# ZX_Gesture_Sensor_SMD.net
KiCad netlist of a schematic drawn in EAGLE
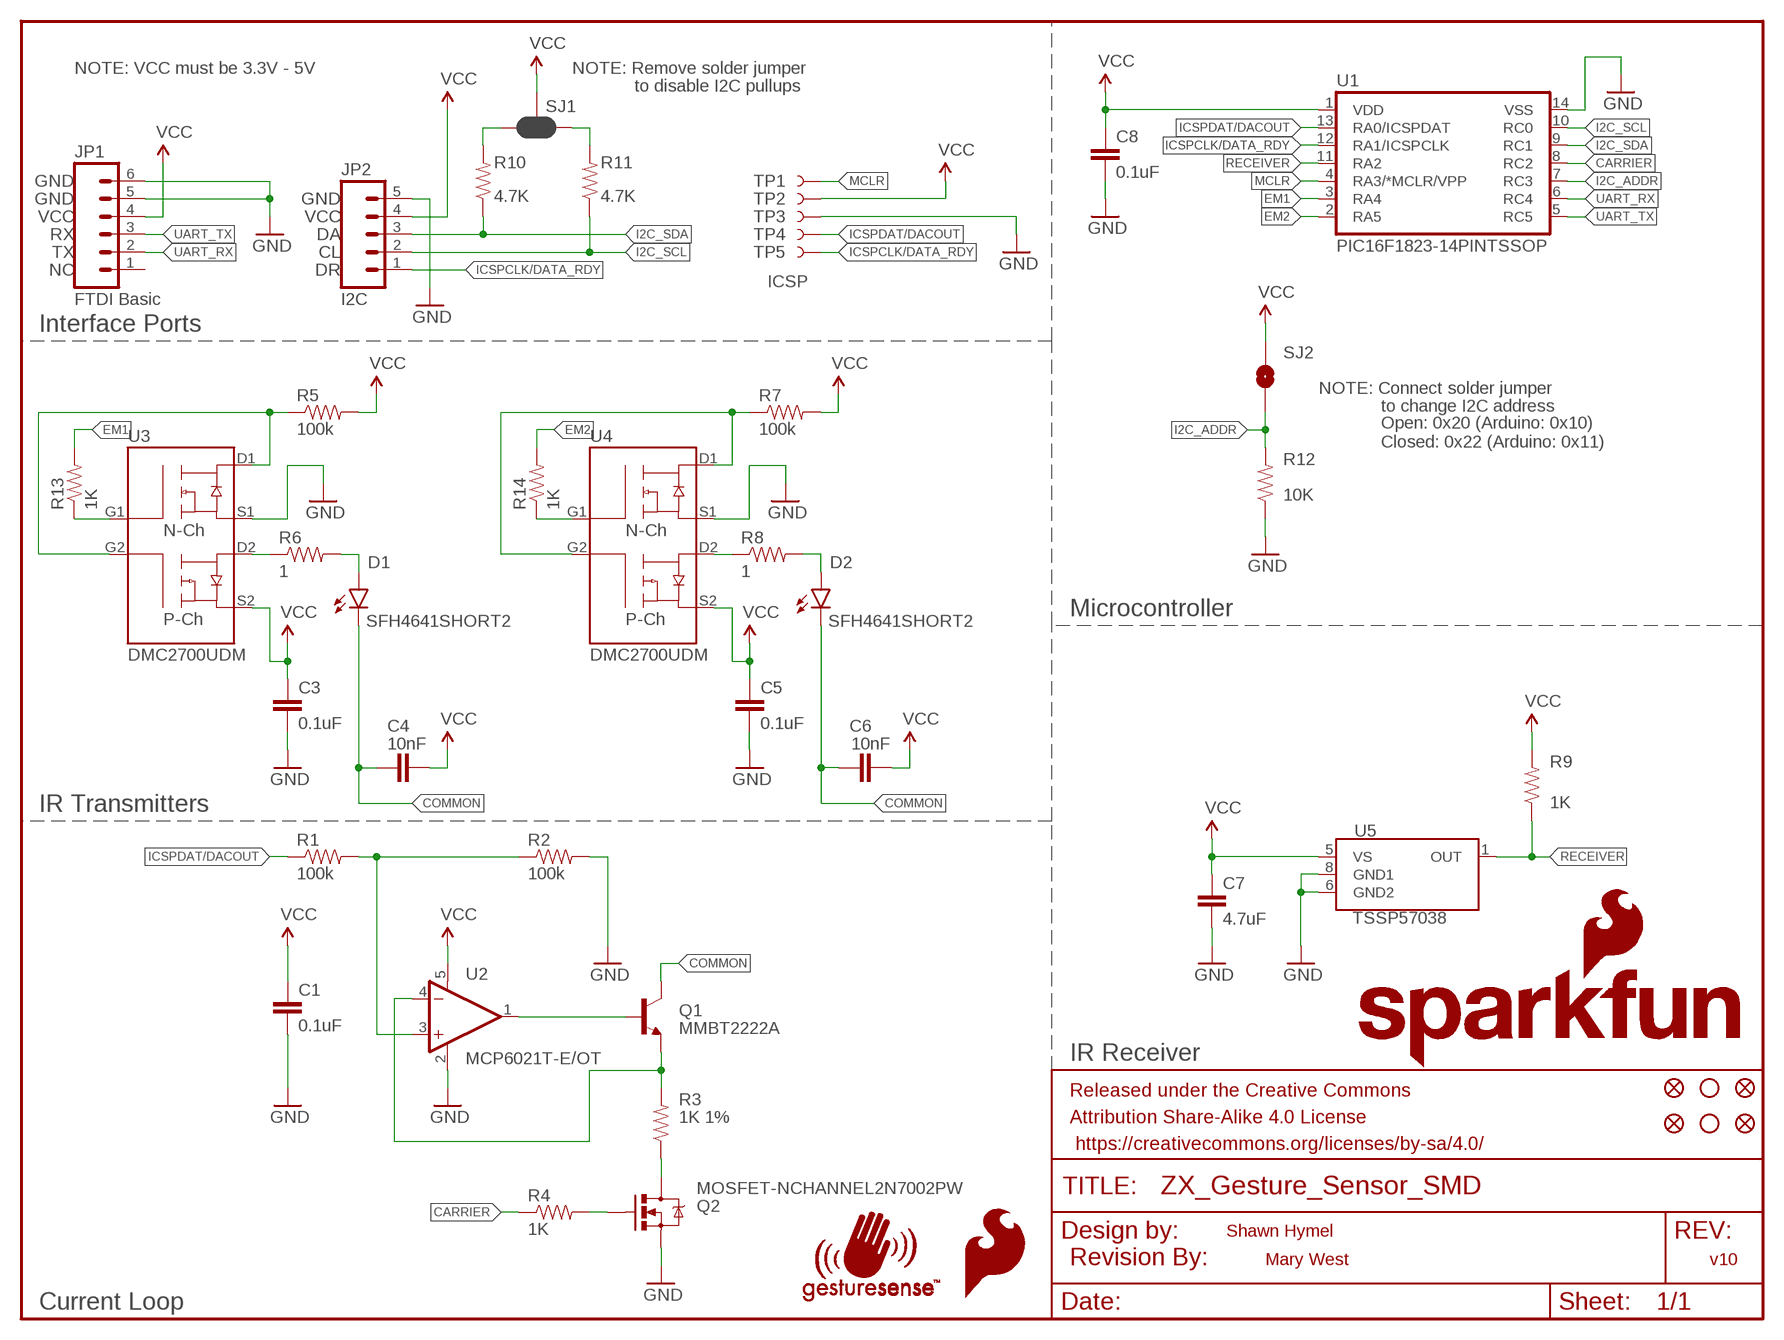
[diagram p0: schematic, sheet 1]

(export (version "E")
  (design (tool "Eeschema 10.0.6"))
  (components
    (comp (ref "C1")
      (value "0.1uF")
      (footprint "eagle-import:0603-CAP")
      (libsource (lib "eagle-import") (part "0.1UF-25V(+80/-20%)(0603)"))
    )
    (comp (ref "C3")
      (value "0.1uF")
      (footprint "eagle-import:0603-CAP")
      (libsource (lib "eagle-import") (part "0.1UF-25V(+80/-20%)(0603)"))
    )
    (comp (ref "C4")
      (value "10nF")
      (footprint "eagle-import:0603-CAP")
      (libsource (lib "eagle-import") (part "10NF/10000PF-50V-10%(0603)"))
    )
    (comp (ref "C5")
      (value "0.1uF")
      (footprint "eagle-import:0603-CAP")
      (libsource (lib "eagle-import") (part "0.1UF-25V(+80/-20%)(0603)"))
    )
    (comp (ref "C6")
      (value "10nF")
      (footprint "eagle-import:0603-CAP")
      (libsource (lib "eagle-import") (part "10NF/10000PF-50V-10%(0603)"))
    )
    (comp (ref "C7")
      (value "4.7uF")
      (footprint "eagle-import:0603-CAP")
      (libsource (lib "eagle-import") (part "4.7UF-6.3V-10%(0603)0603"))
    )
    (comp (ref "C8")
      (value "0.1uF")
      (footprint "eagle-import:0603-CAP")
      (libsource (lib "eagle-import") (part "0.1UF-25V(+80/-20%)(0603)"))
    )
    (comp (ref "D1")
      (value "SFH4641SHORT2")
      (footprint "eagle-import:SFH4641-SHORT2")
      (libsource (lib "eagle-import") (part "SFH4641SHORT2"))
    )
    (comp (ref "D2")
      (value "SFH4641SHORT2")
      (footprint "eagle-import:SFH4641-SHORT2")
      (libsource (lib "eagle-import") (part "SFH4641SHORT2"))
    )
    (comp (ref "FID1")
      (value "FIDUCIALUFIDUCIAL")
      (footprint "eagle-import:MICRO-FIDUCIAL")
      (libsource (lib "eagle-import") (part "FIDUCIALUFIDUCIAL"))
    )
    (comp (ref "FID2")
      (value "FIDUCIALUFIDUCIAL")
      (footprint "eagle-import:MICRO-FIDUCIAL")
      (libsource (lib "eagle-import") (part "FIDUCIALUFIDUCIAL"))
    )
    (comp (ref "FID3")
      (value "FIDUCIALUFIDUCIAL")
      (footprint "eagle-import:MICRO-FIDUCIAL")
      (libsource (lib "eagle-import") (part "FIDUCIALUFIDUCIAL"))
    )
    (comp (ref "FID4")
      (value "FIDUCIALUFIDUCIAL")
      (footprint "eagle-import:MICRO-FIDUCIAL")
      (libsource (lib "eagle-import") (part "FIDUCIALUFIDUCIAL"))
    )
    (comp (ref "FRAME1")
      (value "FRAME-LETTER")
      (footprint "eagle-import:CREATIVE_COMMONS")
      (libsource (lib "eagle-import") (part "FRAME-LETTER"))
    )
    (comp (ref "JP1")
      (value "M06NO_SILK_FEMALE_PTH")
      (footprint "eagle-import:1X06_NO_SILK")
      (libsource (lib "eagle-import") (part "M06NO_SILK_FEMALE_PTH"))
    )
    (comp (ref "JP2")
      (value "M05PTH")
      (footprint "eagle-import:1X05")
      (libsource (lib "eagle-import") (part "M05PTH"))
    )
    (comp (ref "LOGO1")
      (value "REVISION")
      (footprint "eagle-import:REVISION")
      (libsource (lib "eagle-import") (part "REVISION"))
    )
    (comp (ref "LOGO2")
      (value "SFE_LOGO_FLAME.1_INCH")
      (footprint "eagle-import:SFE_LOGO_FLAME_.1")
      (libsource (lib "eagle-import") (part "SFE_LOGO_FLAME.1_INCH"))
    )
    (comp (ref "Q1")
      (value "MMBT2222A")
      (footprint "eagle-import:SOT23-3")
      (libsource (lib "eagle-import") (part "TRANSISTOR_NPNMMBT2222A"))
    )
    (comp (ref "Q2")
      (value "MOSFET-NCHANNEL2N7002PW")
      (footprint "eagle-import:SOT323")
      (libsource (lib "eagle-import") (part "MOSFET-NCHANNEL2N7002PW"))
    )
    (comp (ref "R1")
      (value "100k")
      (footprint "eagle-import:0603-RES")
      (libsource (lib "eagle-import") (part "100KOHM-1/10W-1%(0603)"))
    )
    (comp (ref "R2")
      (value "100k")
      (footprint "eagle-import:0603-RES")
      (libsource (lib "eagle-import") (part "100KOHM-1/10W-1%(0603)"))
    )
    (comp (ref "R3")
      (value "1K 1%")
      (footprint "eagle-import:0603-RES")
      (libsource (lib "eagle-import") (part "1KOHM-1/10W-1%(0603)"))
    )
    (comp (ref "R4")
      (value "1K")
      (footprint "eagle-import:0603-RES")
      (libsource (lib "eagle-import") (part "1KOHM-1/10W-1%(0603)"))
    )
    (comp (ref "R5")
      (value "100k")
      (footprint "eagle-import:0603-RES")
      (libsource (lib "eagle-import") (part "100KOHM-1/10W-1%(0603)"))
    )
    (comp (ref "R6")
      (value "1")
      (footprint "eagle-import:0603-RES")
      (libsource (lib "eagle-import") (part "1OHM1/10W1%(0603)"))
    )
    (comp (ref "R7")
      (value "100k")
      (footprint "eagle-import:0603-RES")
      (libsource (lib "eagle-import") (part "100KOHM-1/10W-1%(0603)"))
    )
    (comp (ref "R8")
      (value "1")
      (footprint "eagle-import:0603-RES")
      (libsource (lib "eagle-import") (part "1OHM1/10W1%(0603)"))
    )
    (comp (ref "R9")
      (value "1K")
      (footprint "eagle-import:0603-RES")
      (libsource (lib "eagle-import") (part "1KOHM-1/10W-1%(0603)"))
    )
    (comp (ref "R10")
      (value "4.7K")
      (footprint "eagle-import:0603-RES")
      (libsource (lib "eagle-import") (part "4.7KOHM-1/10W-1%(0603)"))
    )
    (comp (ref "R11")
      (value "4.7K")
      (footprint "eagle-import:0603-RES")
      (libsource (lib "eagle-import") (part "4.7KOHM-1/10W-1%(0603)"))
    )
    (comp (ref "R12")
      (value "10K")
      (footprint "eagle-import:0603-RES")
      (libsource (lib "eagle-import") (part "10KOHM-1/10W-1%(0603)0603"))
    )
    (comp (ref "R13")
      (value "1K")
      (footprint "eagle-import:0603-RES")
      (libsource (lib "eagle-import") (part "1KOHM-1/10W-1%(0603)"))
    )
    (comp (ref "R14")
      (value "1K")
      (footprint "eagle-import:0603-RES")
      (libsource (lib "eagle-import") (part "1KOHM-1/10W-1%(0603)"))
    )
    (comp (ref "SJ1")
      (value "JUMPER-PAD-3-NC_BY_PASTE")
      (footprint "eagle-import:PAD-JUMPER-3-NC_BY_PASTE_YES_SILK_FULL_BOX")
      (libsource (lib "eagle-import") (part "JUMPER-PAD-3-NC_BY_PASTE"))
    )
    (comp (ref "SJ2")
      (value "JUMPER-PAD-2-NOYES_SILK")
      (footprint "eagle-import:PAD-JUMPER-2-NO_YES_SILK")
      (libsource (lib "eagle-import") (part "JUMPER-PAD-2-NOYES_SILK"))
    )
    (comp (ref "STANDOFF1")
      (value "STAND-OFF")
      (footprint "eagle-import:STAND-OFF")
      (libsource (lib "eagle-import") (part "STAND-OFF"))
    )
    (comp (ref "STANDOFF2")
      (value "STAND-OFF")
      (footprint "eagle-import:STAND-OFF")
      (libsource (lib "eagle-import") (part "STAND-OFF"))
    )
    (comp (ref "TP1")
      (value "TEST-POINT3X4")
      (footprint "eagle-import:PAD.03X.04")
      (libsource (lib "eagle-import") (part "TEST-POINT3X4"))
    )
    (comp (ref "TP2")
      (value "TEST-POINT3X4")
      (footprint "eagle-import:PAD.03X.04")
      (libsource (lib "eagle-import") (part "TEST-POINT3X4"))
    )
    (comp (ref "TP3")
      (value "TEST-POINT3X4")
      (footprint "eagle-import:PAD.03X.04")
      (libsource (lib "eagle-import") (part "TEST-POINT3X4"))
    )
    (comp (ref "TP4")
      (value "TEST-POINT3X4")
      (footprint "eagle-import:PAD.03X.04")
      (libsource (lib "eagle-import") (part "TEST-POINT3X4"))
    )
    (comp (ref "TP5")
      (value "TEST-POINT3X4")
      (footprint "eagle-import:PAD.03X.04")
      (libsource (lib "eagle-import") (part "TEST-POINT3X4"))
    )
    (comp (ref "U$5")
      (value "SFE_LOGO_NAME_FLAME.1_INCH")
      (footprint "eagle-import:SFE_LOGO_NAME_FLAME_.1")
      (libsource (lib "eagle-import") (part "SFE_LOGO_NAME_FLAME.1_INCH"))
    )
    (comp (ref "U$6")
      (value "GESTURESENSE_LOGOSTEXT")
      (footprint "eagle-import:GESTURESENSE_TEXT")
      (libsource (lib "eagle-import") (part "GESTURESENSE_LOGOSTEXT"))
    )
    (comp (ref "U1")
      (value "PIC16F1823-14PINTSSOP")
      (footprint "eagle-import:TSSOP14")
      (libsource (lib "eagle-import") (part "PIC16F1823-14PINTSSOP"))
    )
    (comp (ref "U2")
      (value "MCP6021T-E/OT")
      (footprint "eagle-import:SOT23-5")
      (libsource (lib "eagle-import") (part "MCP6021T-E/OT"))
    )
    (comp (ref "U3")
      (value "DMC2700UDM")
      (footprint "eagle-import:SOT26")
      (libsource (lib "eagle-import") (part "DMC2700UDM"))
    )
    (comp (ref "U4")
      (value "DMC2700UDM")
      (footprint "eagle-import:SOT26")
      (libsource (lib "eagle-import") (part "DMC2700UDM"))
    )
    (comp (ref "U5")
      (value "TSSP57038")
      (footprint "eagle-import:TSOP572")
      (libsource (lib "eagle-import") (part "TSSP57038"))
    )
  )
  (nets
    (net (code "1") (name "CARRIER") (class "Default")
      (node (ref "R4") (pin "1") (pinfunction "1_1") (pintype "passive"))
      (node (ref "U1") (pin "8") (pinfunction "RC2_8") (pintype "bidirectional"))
    )
    (net (code "2") (name "COMMON") (class "Default")
      (node (ref "C4") (pin "1") (pinfunction "1_1") (pintype "passive"))
      (node (ref "C6") (pin "1") (pinfunction "1_1") (pintype "passive"))
      (node (ref "D1") (pin "C") (pinfunction "C_C") (pintype "passive"))
      (node (ref "D2") (pin "C") (pinfunction "C_C") (pintype "passive"))
      (node (ref "Q1") (pin "3") (pinfunction "C_3") (pintype "passive"))
    )
    (net (code "3") (name "EM1") (class "Default")
      (node (ref "R13") (pin "2") (pinfunction "2_2") (pintype "passive"))
      (node (ref "U1") (pin "3") (pinfunction "RA4_3") (pintype "bidirectional"))
    )
    (net (code "4") (name "EM2") (class "Default")
      (node (ref "R14") (pin "2") (pinfunction "2_2") (pintype "passive"))
      (node (ref "U1") (pin "2") (pinfunction "RA5_2") (pintype "bidirectional"))
    )
    (net (code "5") (name "GND") (class "Default")
      (node (ref "C1") (pin "2") (pinfunction "2_2") (pintype "passive"))
      (node (ref "C3") (pin "2") (pinfunction "2_2") (pintype "passive"))
      (node (ref "C5") (pin "2") (pinfunction "2_2") (pintype "passive"))
      (node (ref "C7") (pin "2") (pinfunction "2_2") (pintype "passive"))
      (node (ref "C8") (pin "2") (pinfunction "2_2") (pintype "passive"))
      (node (ref "JP1") (pin "5") (pinfunction "5_5") (pintype "passive"))
      (node (ref "JP1") (pin "6") (pinfunction "6_6") (pintype "passive"))
      (node (ref "JP2") (pin "5") (pinfunction "5_5") (pintype "passive"))
      (node (ref "Q2") (pin "2") (pinfunction "S_2") (pintype "passive"))
      (node (ref "R12") (pin "1") (pinfunction "1_1") (pintype "passive"))
      (node (ref "R2") (pin "2") (pinfunction "2_2") (pintype "passive"))
      (node (ref "TP3") (pin "P$1") (pinfunction "1_P$1") (pintype "bidirectional"))
      (node (ref "U1") (pin "14") (pinfunction "VSS_14") (pintype "power_in"))
      (node (ref "U2") (pin "2") (pinfunction "V-_2") (pintype "power_in"))
      (node (ref "U3") (pin "S1") (pinfunction "S1_S1") (pintype "bidirectional"))
      (node (ref "U4") (pin "S1") (pinfunction "S1_S1") (pintype "bidirectional"))
      (node (ref "U5") (pin "6") (pinfunction "GND2_6") (pintype "bidirectional"))
      (node (ref "U5") (pin "8") (pinfunction "GND1_8") (pintype "bidirectional"))
    )
    (net (code "6") (name "I2C_ADDR") (class "Default")
      (node (ref "R12") (pin "2") (pinfunction "2_2") (pintype "passive"))
      (node (ref "SJ2") (pin "1") (pinfunction "1_1") (pintype "passive"))
      (node (ref "U1") (pin "7") (pinfunction "RC3_7") (pintype "bidirectional"))
    )
    (net (code "7") (name "I2C_SCL") (class "Default")
      (node (ref "JP2") (pin "2") (pinfunction "2_2") (pintype "passive"))
      (node (ref "R11") (pin "1") (pinfunction "1_1") (pintype "passive"))
      (node (ref "U1") (pin "10") (pinfunction "RC0_10") (pintype "bidirectional"))
    )
    (net (code "8") (name "I2C_SDA") (class "Default")
      (node (ref "JP2") (pin "3") (pinfunction "3_3") (pintype "passive"))
      (node (ref "R10") (pin "1") (pinfunction "1_1") (pintype "passive"))
      (node (ref "U1") (pin "9") (pinfunction "RC1_9") (pintype "bidirectional"))
    )
    (net (code "9") (name "ICSPCLK{slash}DATA_RDY") (class "Default")
      (node (ref "JP2") (pin "1") (pinfunction "1_1") (pintype "passive"))
      (node (ref "TP5") (pin "P$1") (pinfunction "1_P$1") (pintype "bidirectional"))
      (node (ref "U1") (pin "12") (pinfunction "RA1/ICSPCLK_12") (pintype "bidirectional"))
    )
    (net (code "10") (name "ICSPDAT{slash}DACOUT") (class "Default")
      (node (ref "R1") (pin "1") (pinfunction "1_1") (pintype "passive"))
      (node (ref "TP4") (pin "P$1") (pinfunction "1_P$1") (pintype "bidirectional"))
      (node (ref "U1") (pin "13") (pinfunction "RA0/ICSPDAT_13") (pintype "bidirectional"))
    )
    (net (code "11") (name "MCLR") (class "Default")
      (node (ref "TP1") (pin "P$1") (pinfunction "1_P$1") (pintype "bidirectional"))
      (node (ref "U1") (pin "4") (pinfunction "RA3/*MCLR/VPP_4") (pintype "input"))
    )
    (net (code "12") (name "Net-(D1-PadA)") (class "Default")
      (node (ref "D1") (pin "A") (pinfunction "A_A") (pintype "passive"))
      (node (ref "R6") (pin "2") (pinfunction "2_2") (pintype "passive"))
    )
    (net (code "13") (name "Net-(D2-PadA)") (class "Default")
      (node (ref "D2") (pin "A") (pinfunction "A_A") (pintype "passive"))
      (node (ref "R8") (pin "2") (pinfunction "2_2") (pintype "passive"))
    )
    (net (code "14") (name "Net-(Q1-B)") (class "Default")
      (node (ref "Q1") (pin "1") (pinfunction "B_1") (pintype "passive"))
      (node (ref "U2") (pin "1") (pinfunction "OUT_1") (pintype "output"))
    )
    (net (code "15") (name "Net-(Q1-E)") (class "Default")
      (node (ref "Q1") (pin "2") (pinfunction "E_2") (pintype "passive"))
      (node (ref "R3") (pin "2") (pinfunction "2_2") (pintype "passive"))
      (node (ref "U2") (pin "4") (pinfunction "-IN_4") (pintype "input"))
    )
    (net (code "16") (name "Net-(Q2-D)") (class "Default")
      (node (ref "Q2") (pin "3") (pinfunction "D_3") (pintype "passive"))
      (node (ref "R3") (pin "1") (pinfunction "1_1") (pintype "passive"))
    )
    (net (code "17") (name "Net-(Q2-G)") (class "Default")
      (node (ref "Q2") (pin "1") (pinfunction "G_1") (pintype "passive"))
      (node (ref "R4") (pin "2") (pinfunction "2_2") (pintype "passive"))
    )
    (net (code "18") (name "Net-(R5-Pad1)") (class "Default")
      (node (ref "R5") (pin "1") (pinfunction "1_1") (pintype "passive"))
      (node (ref "U3") (pin "D1") (pinfunction "D1_D1") (pintype "bidirectional"))
      (node (ref "U3") (pin "G2") (pinfunction "G2_G2") (pintype "bidirectional"))
    )
    (net (code "19") (name "Net-(R6-Pad1)") (class "Default")
      (node (ref "R6") (pin "1") (pinfunction "1_1") (pintype "passive"))
      (node (ref "U3") (pin "D2") (pinfunction "D2_D2") (pintype "bidirectional"))
    )
    (net (code "20") (name "Net-(R7-Pad1)") (class "Default")
      (node (ref "R7") (pin "1") (pinfunction "1_1") (pintype "passive"))
      (node (ref "U4") (pin "D1") (pinfunction "D1_D1") (pintype "bidirectional"))
      (node (ref "U4") (pin "G2") (pinfunction "G2_G2") (pintype "bidirectional"))
    )
    (net (code "21") (name "Net-(R8-Pad1)") (class "Default")
      (node (ref "R8") (pin "1") (pinfunction "1_1") (pintype "passive"))
      (node (ref "U4") (pin "D2") (pinfunction "D2_D2") (pintype "bidirectional"))
    )
    (net (code "22") (name "Net-(R10-Pad2)") (class "Default")
      (node (ref "R10") (pin "2") (pinfunction "2_2") (pintype "passive"))
      (node (ref "SJ1") (pin "3") (pinfunction "3_3") (pintype "passive"))
    )
    (net (code "23") (name "Net-(R11-Pad2)") (class "Default")
      (node (ref "R11") (pin "2") (pinfunction "2_2") (pintype "passive"))
      (node (ref "SJ1") (pin "1") (pinfunction "1_1") (pintype "passive"))
    )
    (net (code "24") (name "Net-(R13-Pad1)") (class "Default")
      (node (ref "R13") (pin "1") (pinfunction "1_1") (pintype "passive"))
      (node (ref "U3") (pin "G1") (pinfunction "G1_G1") (pintype "bidirectional"))
    )
    (net (code "25") (name "Net-(R14-Pad1)") (class "Default")
      (node (ref "R14") (pin "1") (pinfunction "1_1") (pintype "passive"))
      (node (ref "U4") (pin "G1") (pinfunction "G1_G1") (pintype "bidirectional"))
    )
    (net (code "26") (name "Net-(U2-+IN)") (class "Default")
      (node (ref "R1") (pin "2") (pinfunction "2_2") (pintype "passive"))
      (node (ref "R2") (pin "1") (pinfunction "1_1") (pintype "passive"))
      (node (ref "U2") (pin "3") (pinfunction "+IN_3") (pintype "input"))
    )
    (net (code "27") (name "RECEIVER") (class "Default")
      (node (ref "R9") (pin "1") (pinfunction "1_1") (pintype "passive"))
      (node (ref "U1") (pin "11") (pinfunction "RA2_11") (pintype "bidirectional"))
      (node (ref "U5") (pin "1") (pinfunction "OUT_1") (pintype "bidirectional"))
    )
    (net (code "28") (name "UART_RX") (class "Default")
      (node (ref "JP1") (pin "2") (pinfunction "2_2") (pintype "passive"))
      (node (ref "U1") (pin "6") (pinfunction "RC4_6") (pintype "bidirectional"))
    )
    (net (code "29") (name "UART_TX") (class "Default")
      (node (ref "JP1") (pin "3") (pinfunction "3_3") (pintype "passive"))
      (node (ref "U1") (pin "5") (pinfunction "RC5_5") (pintype "bidirectional"))
    )
    (net (code "30") (name "VCC") (class "Default")
      (node (ref "C1") (pin "1") (pinfunction "1_1") (pintype "passive"))
      (node (ref "C3") (pin "1") (pinfunction "1_1") (pintype "passive"))
      (node (ref "C4") (pin "2") (pinfunction "2_2") (pintype "passive"))
      (node (ref "C5") (pin "1") (pinfunction "1_1") (pintype "passive"))
      (node (ref "C6") (pin "2") (pinfunction "2_2") (pintype "passive"))
      (node (ref "C7") (pin "1") (pinfunction "1_1") (pintype "passive"))
      (node (ref "C8") (pin "1") (pinfunction "1_1") (pintype "passive"))
      (node (ref "JP1") (pin "4") (pinfunction "4_4") (pintype "passive"))
      (node (ref "JP2") (pin "4") (pinfunction "4_4") (pintype "passive"))
      (node (ref "R5") (pin "2") (pinfunction "2_2") (pintype "passive"))
      (node (ref "R7") (pin "2") (pinfunction "2_2") (pintype "passive"))
      (node (ref "R9") (pin "2") (pinfunction "2_2") (pintype "passive"))
      (node (ref "SJ1") (pin "2") (pinfunction "2_2") (pintype "passive"))
      (node (ref "SJ2") (pin "2") (pinfunction "2_2") (pintype "passive"))
      (node (ref "TP2") (pin "P$1") (pinfunction "1_P$1") (pintype "bidirectional"))
      (node (ref "U1") (pin "1") (pinfunction "VDD_1") (pintype "power_in"))
      (node (ref "U2") (pin "5") (pinfunction "V+_5") (pintype "power_in"))
      (node (ref "U3") (pin "S2") (pinfunction "S2_S2") (pintype "bidirectional"))
      (node (ref "U4") (pin "S2") (pinfunction "S2_S2") (pintype "bidirectional"))
      (node (ref "U5") (pin "5") (pinfunction "VS_5") (pintype "bidirectional"))
    )
    (net (code "31") (name "unconnected-(JP1-Pad1)") (class "Default")
      (node (ref "JP1") (pin "1") (pinfunction "1_1") (pintype "passive"))
    )
  )
)
